# TOP.net
KiCad netlist of a schematic drawn in Altium Designer
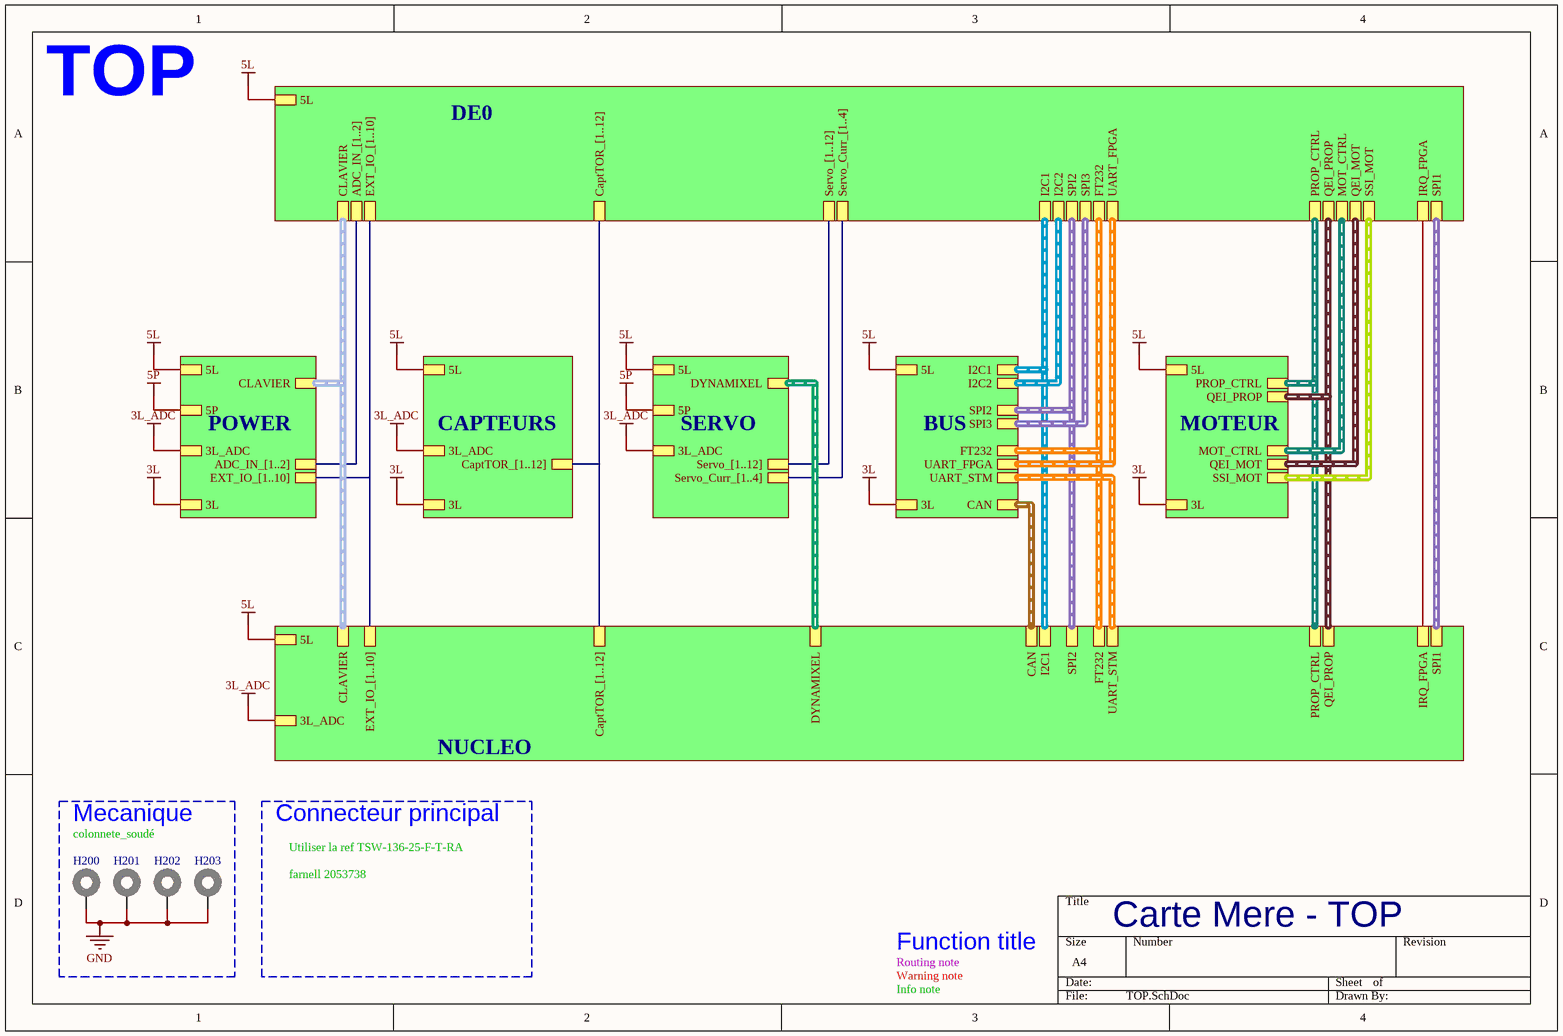
[diagram p0: TOP.SchDoc]

(export (version "E")
  (design (tool "Eeschema 10.0.6"))
  (components
    (comp (ref "H200")
      (value "9774100960")
      (footprint "9774100960")
      (description "WA-SMST SMT Steel Spacer with through hole, OD6mm, ID3.3xL10mm")
      (fields (field (name "MANUFACTURER") "Wurth Elektronik"))
      (libsource (lib "Divers") (part "9774100960"))
    )
    (comp (ref "H201")
      (value "9774100960")
      (footprint "9774100960")
      (description "WA-SMST SMT Steel Spacer with through hole, OD6mm, ID3.3xL10mm")
      (fields (field (name "MANUFACTURER") "Wurth Elektronik"))
      (libsource (lib "Divers") (part "9774100960"))
    )
    (comp (ref "H202")
      (value "9774100960")
      (footprint "9774100960")
      (description "WA-SMST SMT Steel Spacer with through hole, OD6mm, ID3.3xL10mm")
      (fields (field (name "MANUFACTURER") "Wurth Elektronik"))
      (libsource (lib "Divers") (part "9774100960"))
    )
    (comp (ref "H203")
      (value "9774100960")
      (footprint "9774100960")
      (description "WA-SMST SMT Steel Spacer with through hole, OD6mm, ID3.3xL10mm")
      (fields (field (name "MANUFACTURER") "Wurth Elektronik"))
      (libsource (lib "Divers") (part "9774100960"))
    )
  )
  (nets
    (net (code "27") (name "GND") (class "Default")
      (node (ref "H200") (pin "1") (pinfunction "1_1") (pintype "passive"))
      (node (ref "H201") (pin "1") (pinfunction "1_1") (pintype "passive"))
      (node (ref "H202") (pin "1") (pinfunction "1_1") (pintype "passive"))
      (node (ref "H203") (pin "1") (pinfunction "1_1") (pintype "passive"))
    )
  )
)
